# 301_GridPos3.net
KiCad netlist of a schematic drawn in Altium Designer
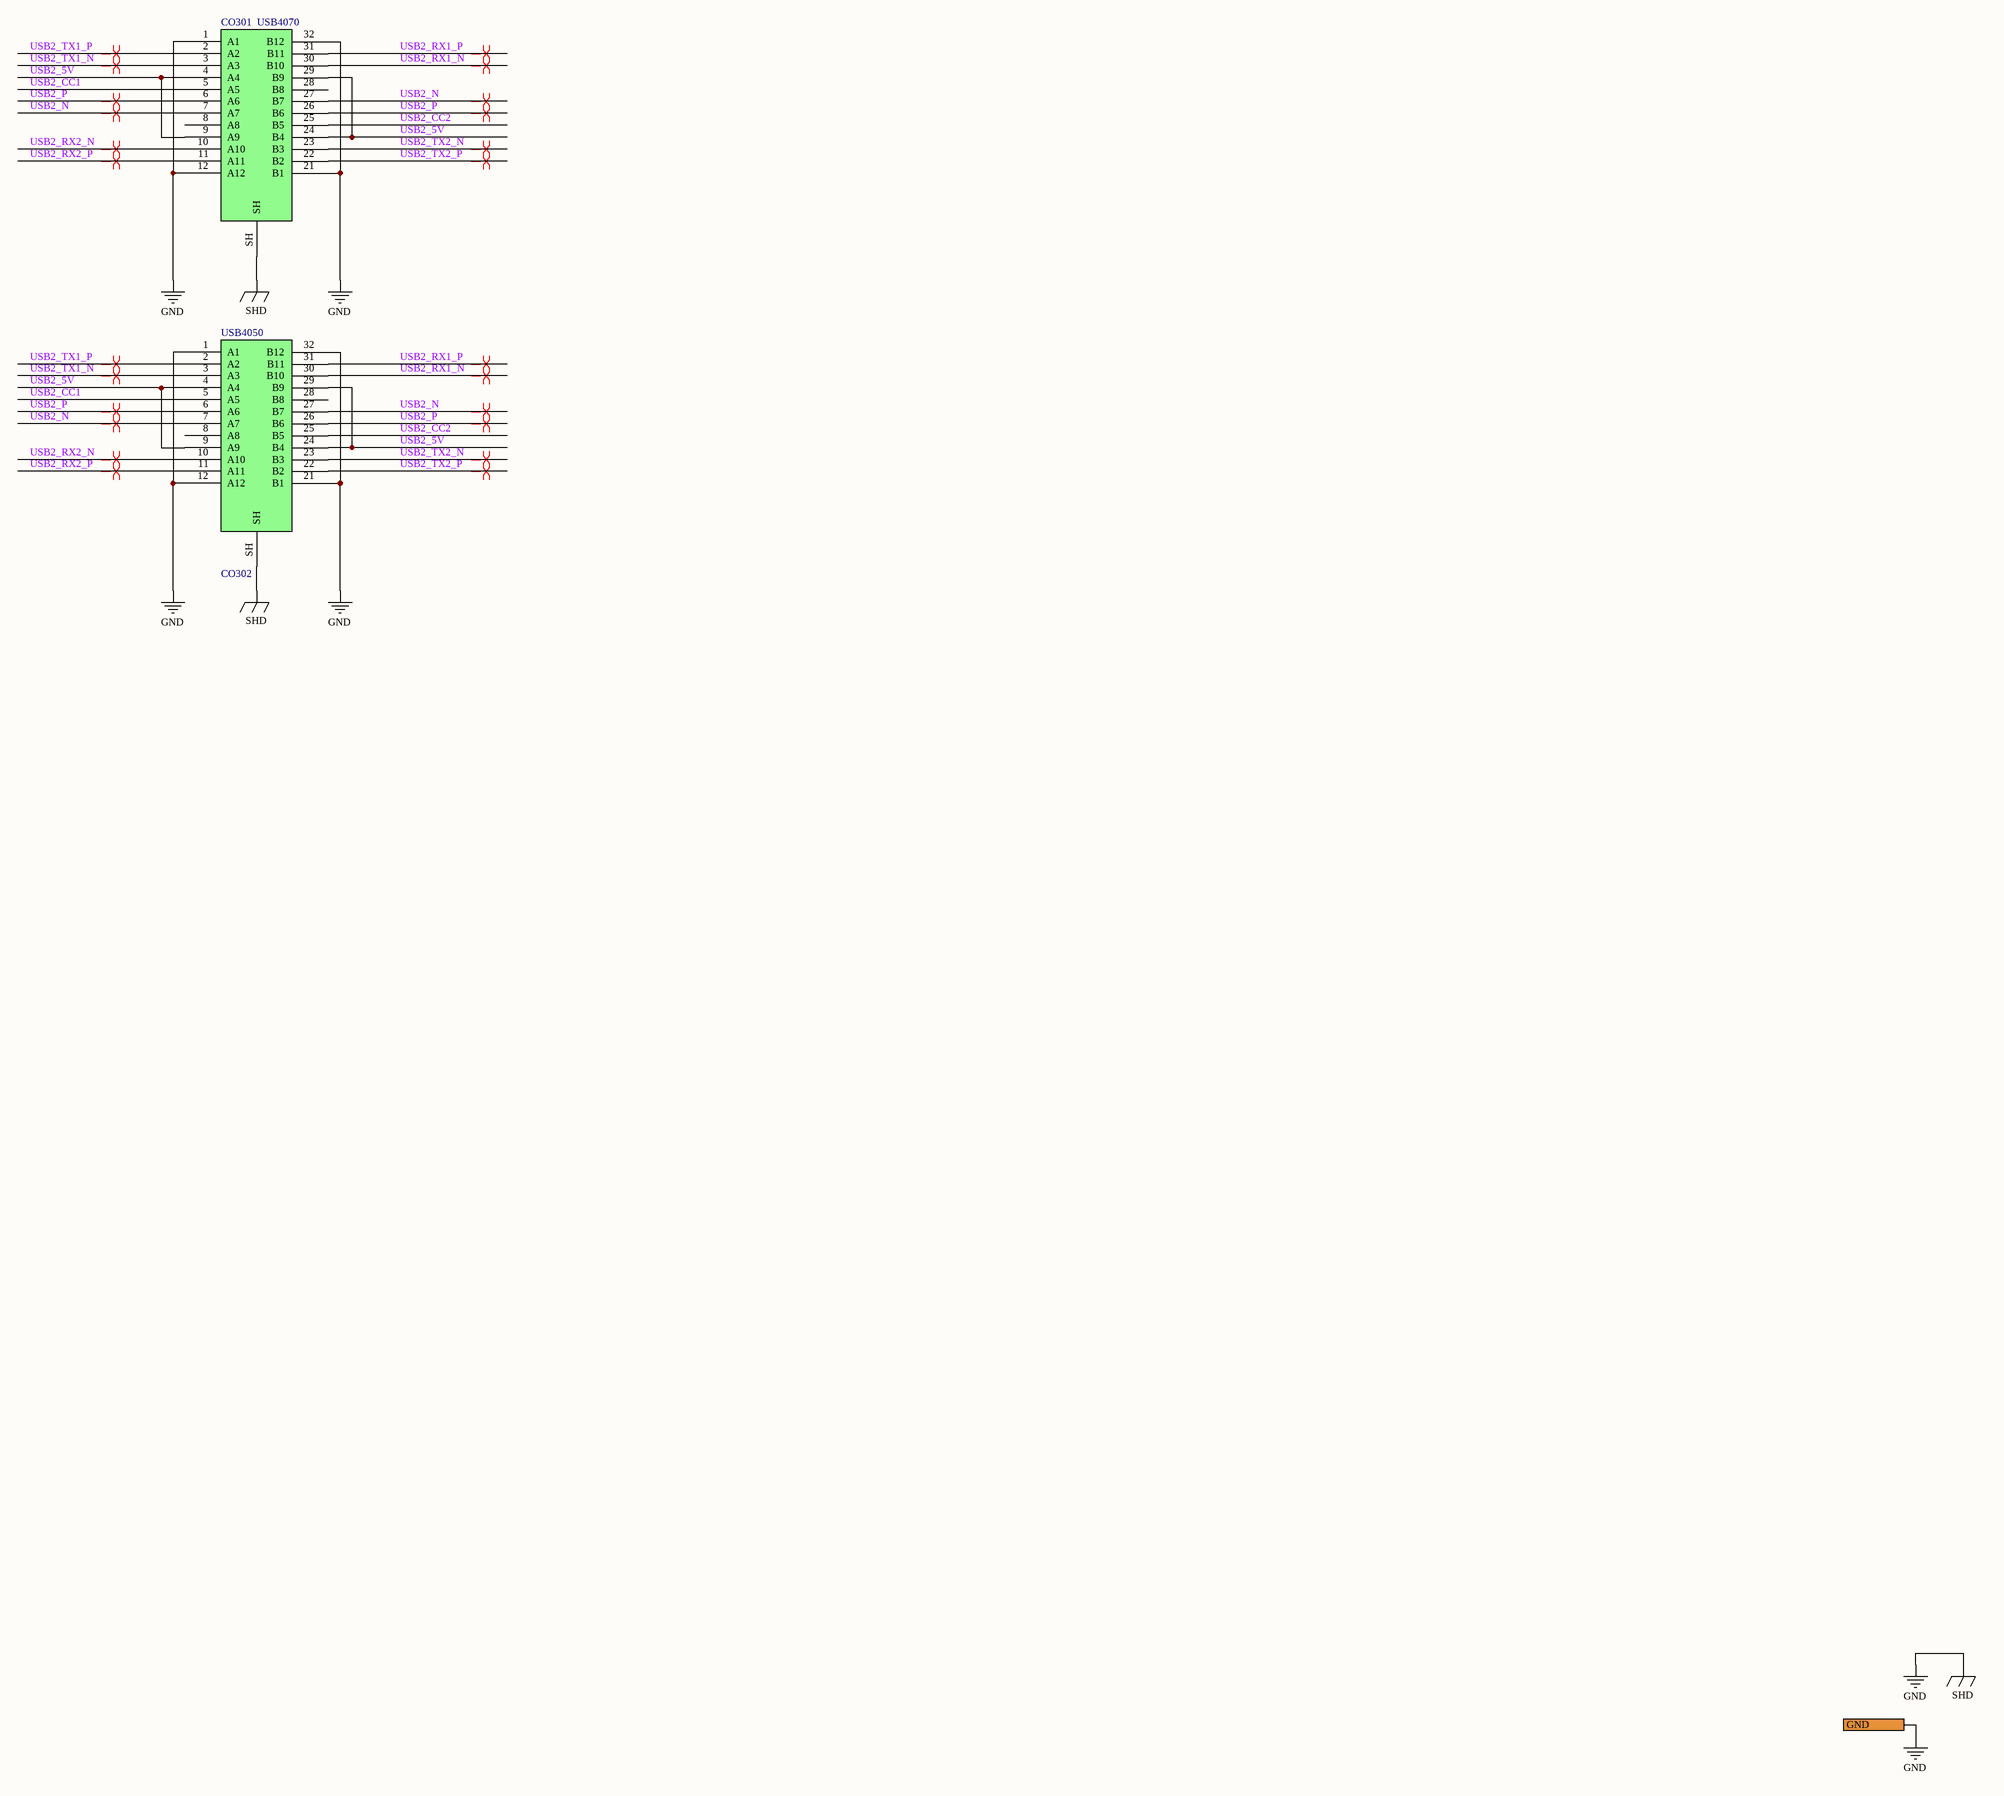
[diagram p0: 301_GridPos3.SchDoc]

(export (version "E")
  (design (tool "Eeschema 10.0.6"))
  (components
    (comp (ref "CO301")
      (value "USB4070")
      (footprint "USB4070-30-C")
      (description "USB4070-30-C")
      (fields (field (name "REFVAL") "USB4070") (field (name "PART NUMBER") "CO0021"))
      (libsource (lib "GTS_Database") (part "USB-CC"))
    )
    (comp (ref "CO302")
      (value "USB4050")
      (footprint "USB4050-30-A")
      (description "USB C connector Receptacle Horizontal")
      (fields
        (field (name "REFVAL") "USB4050")
        (field (name "PART NUMBER") "CO0039")
        (field (name "MANFACTPART") "USB4050-30-A")
      )
      (libsource (lib "") (part "USB-CC_1"))
    )
  )
  (nets
    (net (code "1") (name "/USB2_5V") (class "Default")
      (node (ref "CO301") (pin "24") (pinfunction "B4_24") (pintype "passive"))
      (node (ref "CO301") (pin "29") (pinfunction "B9_29") (pintype "passive"))
      (node (ref "CO301") (pin "4") (pinfunction "A4_4") (pintype "passive"))
      (node (ref "CO301") (pin "9") (pinfunction "A9_9") (pintype "passive"))
      (node (ref "CO302") (pin "24") (pinfunction "B4_24") (pintype "passive"))
      (node (ref "CO302") (pin "29") (pinfunction "B9_29") (pintype "passive"))
      (node (ref "CO302") (pin "4") (pinfunction "A4_4") (pintype "passive"))
      (node (ref "CO302") (pin "9") (pinfunction "A9_9") (pintype "passive"))
    )
    (net (code "2") (name "/USB2_CC1") (class "Default")
      (node (ref "CO301") (pin "5") (pinfunction "A5_5") (pintype "passive"))
      (node (ref "CO302") (pin "5") (pinfunction "A5_5") (pintype "passive"))
    )
    (net (code "3") (name "/USB2_CC2") (class "Default")
      (node (ref "CO301") (pin "25") (pinfunction "B5_25") (pintype "passive"))
      (node (ref "CO302") (pin "25") (pinfunction "B5_25") (pintype "passive"))
    )
    (net (code "4") (name "/USB2_N") (class "Default")
      (node (ref "CO301") (pin "27") (pinfunction "B7_27") (pintype "passive"))
      (node (ref "CO301") (pin "7") (pinfunction "A7_7") (pintype "passive"))
      (node (ref "CO302") (pin "27") (pinfunction "B7_27") (pintype "passive"))
      (node (ref "CO302") (pin "7") (pinfunction "A7_7") (pintype "passive"))
    )
    (net (code "5") (name "/USB2_P") (class "Default")
      (node (ref "CO301") (pin "26") (pinfunction "B6_26") (pintype "passive"))
      (node (ref "CO301") (pin "6") (pinfunction "A6_6") (pintype "passive"))
      (node (ref "CO302") (pin "26") (pinfunction "B6_26") (pintype "passive"))
      (node (ref "CO302") (pin "6") (pinfunction "A6_6") (pintype "passive"))
    )
    (net (code "6") (name "/USB2_RX1_N") (class "Default")
      (node (ref "CO301") (pin "30") (pinfunction "B10_30") (pintype "passive"))
      (node (ref "CO302") (pin "30") (pinfunction "B10_30") (pintype "passive"))
    )
    (net (code "7") (name "/USB2_RX1_P") (class "Default")
      (node (ref "CO301") (pin "31") (pinfunction "B11_31") (pintype "passive"))
      (node (ref "CO302") (pin "31") (pinfunction "B11_31") (pintype "passive"))
    )
    (net (code "8") (name "/USB2_RX2_N") (class "Default")
      (node (ref "CO301") (pin "10") (pinfunction "A10_10") (pintype "passive"))
      (node (ref "CO302") (pin "10") (pinfunction "A10_10") (pintype "passive"))
    )
    (net (code "9") (name "/USB2_RX2_P") (class "Default")
      (node (ref "CO301") (pin "11") (pinfunction "A11_11") (pintype "passive"))
      (node (ref "CO302") (pin "11") (pinfunction "A11_11") (pintype "passive"))
    )
    (net (code "10") (name "/USB2_TX1_N") (class "Default")
      (node (ref "CO301") (pin "3") (pinfunction "A3_3") (pintype "passive"))
      (node (ref "CO302") (pin "3") (pinfunction "A3_3") (pintype "passive"))
    )
    (net (code "11") (name "/USB2_TX1_P") (class "Default")
      (node (ref "CO301") (pin "2") (pinfunction "A2_2") (pintype "passive"))
      (node (ref "CO302") (pin "2") (pinfunction "A2_2") (pintype "passive"))
    )
    (net (code "12") (name "/USB2_TX2_N") (class "Default")
      (node (ref "CO301") (pin "23") (pinfunction "B3_23") (pintype "passive"))
      (node (ref "CO302") (pin "23") (pinfunction "B3_23") (pintype "passive"))
    )
    (net (code "13") (name "/USB2_TX2_P") (class "Default")
      (node (ref "CO301") (pin "22") (pinfunction "B2_22") (pintype "passive"))
      (node (ref "CO302") (pin "22") (pinfunction "B2_22") (pintype "passive"))
    )
    (net (code "14") (name "GND") (class "Default")
      (node (ref "CO301") (pin "1") (pinfunction "A1_1") (pintype "passive"))
      (node (ref "CO301") (pin "12") (pinfunction "A12_12") (pintype "passive"))
      (node (ref "CO301") (pin "21") (pinfunction "B1_21") (pintype "passive"))
      (node (ref "CO301") (pin "32") (pinfunction "B12_32") (pintype "passive"))
      (node (ref "CO301") (pin "SH") (pinfunction "SH_SH") (pintype "power_in"))
      (node (ref "CO302") (pin "1") (pinfunction "A1_1") (pintype "passive"))
      (node (ref "CO302") (pin "12") (pinfunction "A12_12") (pintype "passive"))
      (node (ref "CO302") (pin "21") (pinfunction "B1_21") (pintype "passive"))
      (node (ref "CO302") (pin "32") (pinfunction "B12_32") (pintype "passive"))
      (node (ref "CO302") (pin "SH") (pinfunction "SH_SH") (pintype "power_in"))
    )
    (net (code "15") (name "unconnected-(CO301-A8-Pad8)") (class "Default")
      (node (ref "CO301") (pin "8") (pinfunction "A8_8") (pintype "passive"))
    )
    (net (code "16") (name "unconnected-(CO301-B8-Pad28)") (class "Default")
      (node (ref "CO301") (pin "28") (pinfunction "B8_28") (pintype "passive"))
    )
    (net (code "17") (name "unconnected-(CO302-A8-Pad8)") (class "Default")
      (node (ref "CO302") (pin "8") (pinfunction "A8_8") (pintype "passive"))
    )
    (net (code "18") (name "unconnected-(CO302-B8-Pad28)") (class "Default")
      (node (ref "CO302") (pin "28") (pinfunction "B8_28") (pintype "passive"))
    )
  )
)
